# 03_POWER.net
KiCad netlist of a schematic drawn in Altium Designer
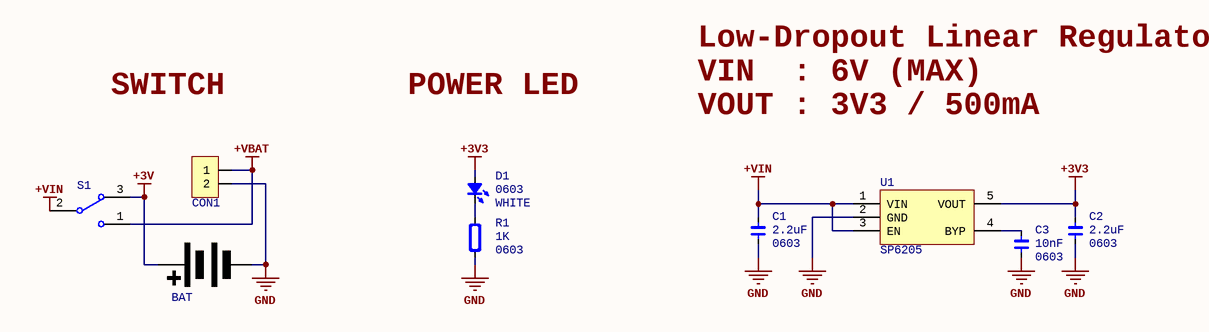
[diagram p0: [03] POWER.SchDoc]

(export (version "E")
  (design (tool "Eeschema 10.0.6"))
  (components
    (comp (ref "BAT")
      (value "Battery")
      (footprint "PCB_Battery:CR2032-1")
      (libsource (lib "SCH_Battery") (part "Battery"))
    )
    (comp (ref "C1")
      (value "2.2uF")
      (footprint "PCB_PassiveCap:CAP_0603")
      (description "Capacitor")
      (fields (field (name "TYPE") "0603"))
      (libsource (lib "SCH_Passive") (part "Cap_0603"))
    )
    (comp (ref "C2")
      (value "2.2uF")
      (footprint "PCB_PassiveCap:CAP_0603")
      (description "Capacitor")
      (fields (field (name "TYPE") "0603"))
      (libsource (lib "SCH_Passive") (part "Cap_0603"))
    )
    (comp (ref "C3")
      (value "10nF")
      (footprint "PCB_PassiveCap:CAP_0603")
      (description "Capacitor")
      (fields (field (name "TYPE") "0603"))
      (libsource (lib "SCH_Passive") (part "Cap_0603"))
    )
    (comp (ref "CON1")
      (value "MX1.25_2P")
      (footprint "PCB_Connector:MX1.25_S90_2P")
      (description "MX")
      (libsource (lib "SCH_Connector") (part "MX1.25_2P"))
    )
    (comp (ref "D1")
      (value "WHITE")
      (footprint "PCB_ActiveLED:LED_0603_YELLOW")
      (description "LED")
      (fields (field (name "TYPE") "0603"))
      (libsource (lib "SCH_Active") (part "LED_0603"))
    )
    (comp (ref "R1")
      (value "1K")
      (footprint "PCB_PassiveRes:RES_0603")
      (description "Resistor")
      (fields (field (name "TYPE") "0603"))
      (libsource (lib "SCH_Passive") (part "Res_0603"))
    )
    (comp (ref "S1")
      (value "SPDT 3P")
      (footprint "PCB_Switch:SwitchSPDT_2.8X6.6_90")
      (description "Switch")
      (libsource (lib "SCH_Switch") (part "SwitchSPDT_2.8x6.6_90"))
    )
    (comp (ref "U1")
      (value "SP6205")
      (footprint "PCB_IntegratedCircuit:SOT23-5")
      (description "Power")
      (libsource (lib "SCH_IntegratedCircuit") (part "SP6205"))
    )
  )
  (nets
    (net (code "1") (name "+3V") (class "Default")
      (node (ref "BAT") (pin "2") (pinfunction "+_2") (pintype "passive"))
      (node (ref "S1") (pin "3") (pinfunction "3_3") (pintype "passive"))
    )
    (net (code "2") (name "+3V3") (class "Default")
      (node (ref "C2") (pin "2") (pinfunction "2_2") (pintype "passive"))
      (node (ref "D1") (pin "1") (pinfunction "A_1") (pintype "passive"))
      (node (ref "U1") (pin "5") (pinfunction "VOUT_5") (pintype "passive"))
    )
    (net (code "3") (name "+VBAT") (class "Default")
      (node (ref "CON1") (pin "1") (pinfunction "1_1") (pintype "passive"))
      (node (ref "S1") (pin "1") (pinfunction "1_1") (pintype "passive"))
    )
    (net (code "4") (name "+VIN") (class "Default")
      (node (ref "C1") (pin "2") (pinfunction "2_2") (pintype "passive"))
      (node (ref "S1") (pin "2") (pinfunction "2_2") (pintype "passive"))
      (node (ref "U1") (pin "1") (pinfunction "VIN_1") (pintype "passive"))
      (node (ref "U1") (pin "3") (pinfunction "EN_3") (pintype "power_in"))
    )
    (net (code "5") (name "GND") (class "Default")
      (node (ref "BAT") (pin "1") (pinfunction "-_1") (pintype "passive"))
      (node (ref "C1") (pin "1") (pinfunction "1_1") (pintype "passive"))
      (node (ref "C2") (pin "1") (pinfunction "1_1") (pintype "passive"))
      (node (ref "C3") (pin "1") (pinfunction "1_1") (pintype "passive"))
      (node (ref "CON1") (pin "2") (pinfunction "2_2") (pintype "passive"))
      (node (ref "R1") (pin "1") (pinfunction "1_1") (pintype "passive"))
      (node (ref "U1") (pin "2") (pinfunction "GND_2") (pintype "passive"))
    )
    (net (code "6") (name "Net-(D1-K)") (class "Default")
      (node (ref "D1") (pin "2") (pinfunction "K_2") (pintype "passive"))
      (node (ref "R1") (pin "2") (pinfunction "2_2") (pintype "passive"))
    )
    (net (code "7") (name "Net-(U1-BYP)") (class "Default")
      (node (ref "C3") (pin "2") (pinfunction "2_2") (pintype "passive"))
      (node (ref "U1") (pin "4") (pinfunction "BYP_4") (pintype "passive"))
    )
  )
)
